# drive_subsystem.net
KiCad netlist of a schematic drawn in EAGLE
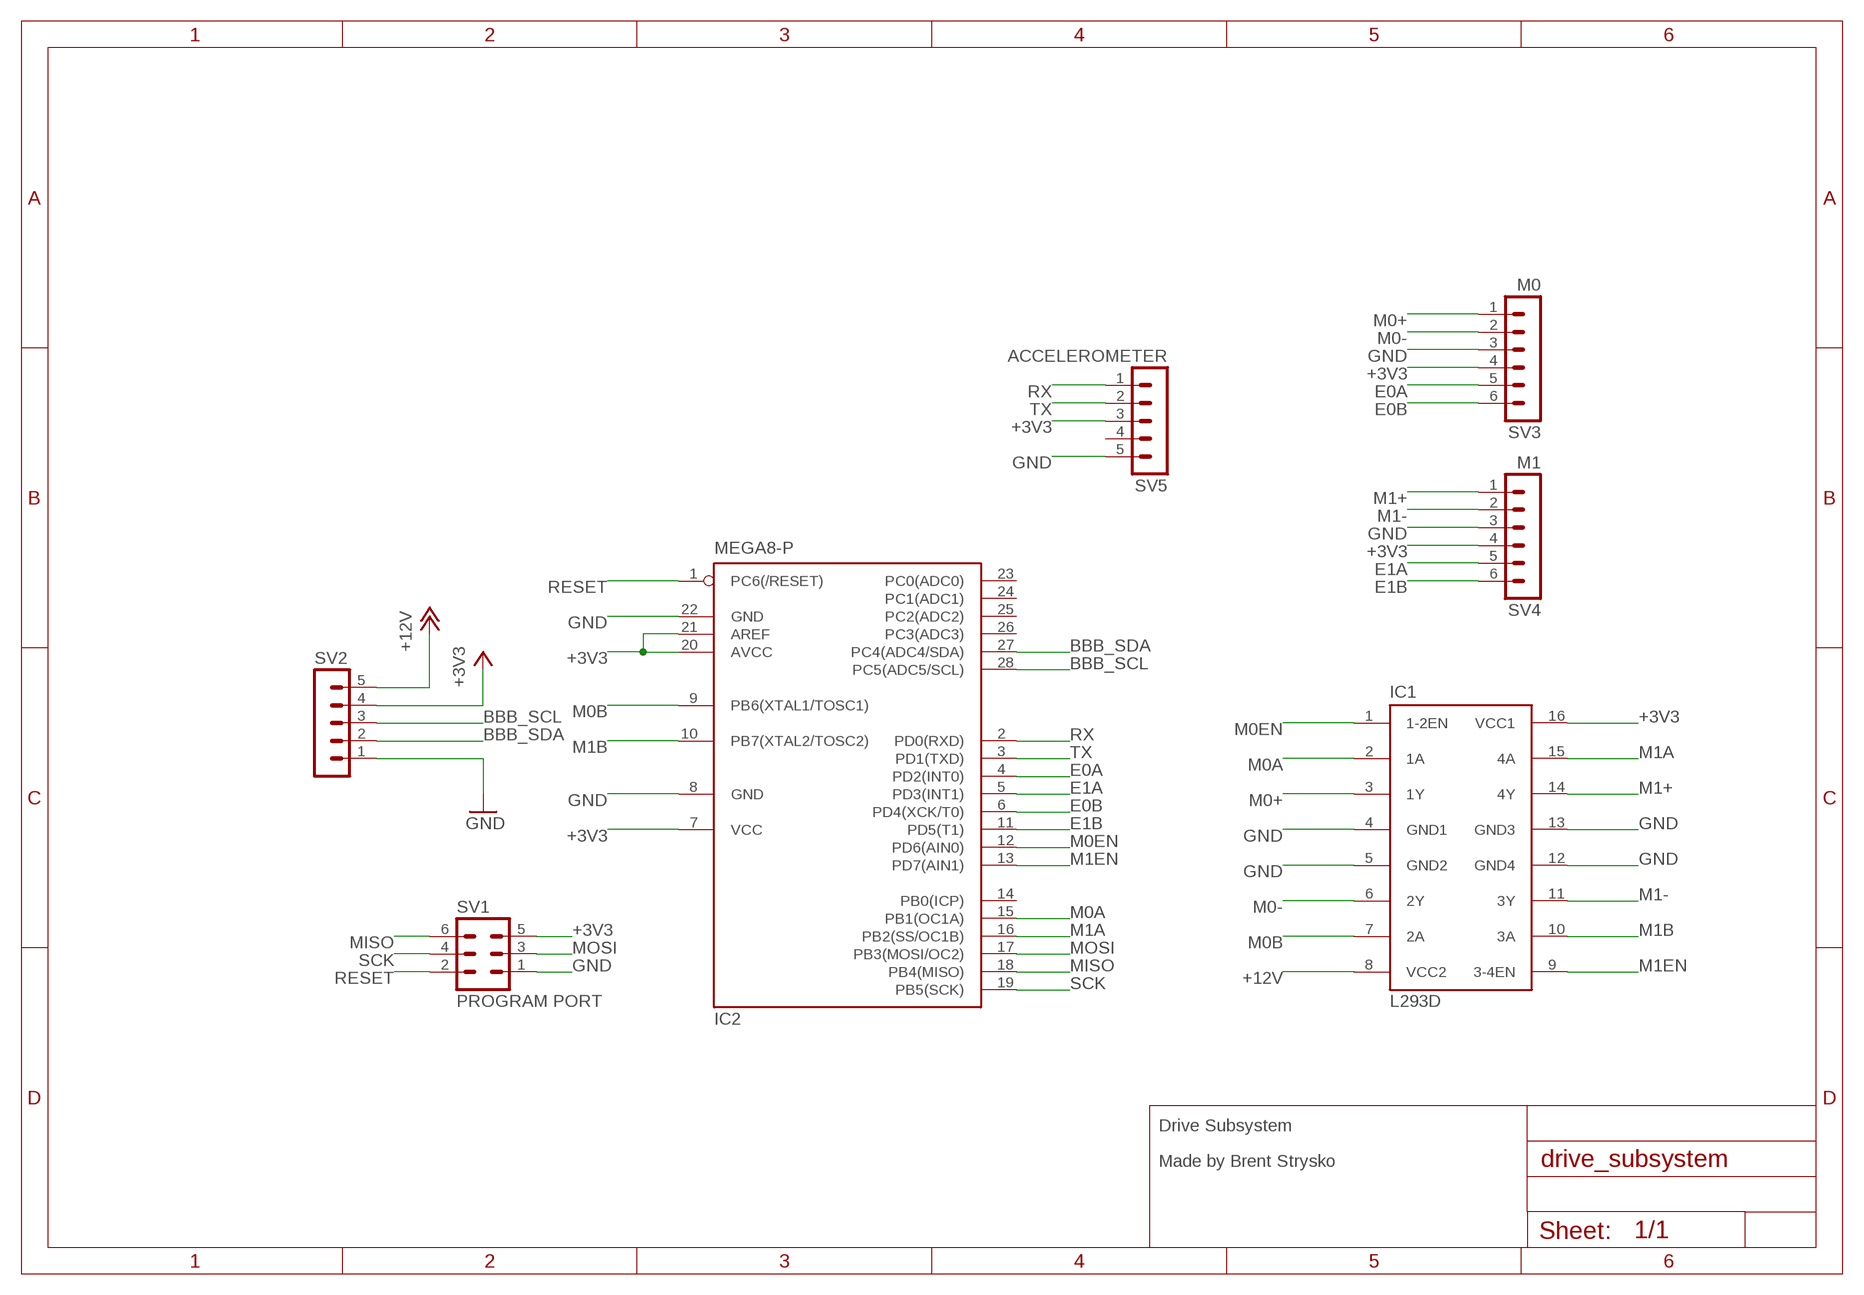
[diagram p0: schematic, sheet 1]

(export (version "E")
  (design (tool "Eeschema 10.0.6"))
  (components
    (comp (ref "IC1")
      (value "L293D")
      (footprint "eagle-import:DIL16")
      (libsource (lib "eagle-import") (part "L293D"))
    )
    (comp (ref "IC2")
      (value "MEGA8-P")
      (footprint "eagle-import:DIL28-3")
      (libsource (lib "eagle-import") (part "MEGA8-P"))
    )
    (comp (ref "SV1")
      (value "PROGRAM PORT")
      (footprint "eagle-import:MA03-2")
      (libsource (lib "eagle-import") (part "MA03-2"))
    )
    (comp (ref "SV2")
      (value "MA05-1")
      (footprint "eagle-import:MA05-1")
      (libsource (lib "eagle-import") (part "MA05-1"))
    )
    (comp (ref "SV3")
      (value "M0")
      (footprint "eagle-import:MA06-1")
      (libsource (lib "eagle-import") (part "MA06-1"))
    )
    (comp (ref "SV4")
      (value "M1")
      (footprint "eagle-import:MA06-1")
      (libsource (lib "eagle-import") (part "MA06-1"))
    )
    (comp (ref "SV5")
      (value "ACCELEROMETER")
      (footprint "eagle-import:MA05-1")
      (libsource (lib "eagle-import") (part "MA05-1"))
    )
  )
  (nets
    (net (code "1") (name "+3V3") (class "Default")
      (node (ref "IC1") (pin "16") (pinfunction "VCC1_16") (pintype "power_in"))
      (node (ref "IC2") (pin "20") (pinfunction "AVCC_20") (pintype "power_in"))
      (node (ref "IC2") (pin "21") (pinfunction "AREF_21") (pintype "passive"))
      (node (ref "IC2") (pin "7") (pinfunction "VCC_7") (pintype "power_in"))
      (node (ref "SV1") (pin "5") (pinfunction "5_5") (pintype "passive"))
      (node (ref "SV2") (pin "4") (pinfunction "4_4") (pintype "passive"))
      (node (ref "SV3") (pin "4") (pinfunction "4_4") (pintype "passive"))
      (node (ref "SV4") (pin "4") (pinfunction "4_4") (pintype "passive"))
      (node (ref "SV5") (pin "3") (pinfunction "3_3") (pintype "passive"))
    )
    (net (code "2") (name "+12V") (class "Default")
      (node (ref "IC1") (pin "8") (pinfunction "VCC2_8") (pintype "power_in"))
      (node (ref "SV2") (pin "5") (pinfunction "5_5") (pintype "passive"))
    )
    (net (code "3") (name "/BBB_SCL") (class "Default")
      (node (ref "IC2") (pin "28") (pinfunction "PC5(ADC5/SCL)_28") (pintype "bidirectional"))
      (node (ref "SV2") (pin "3") (pinfunction "3_3") (pintype "passive"))
    )
    (net (code "4") (name "/BBB_SDA") (class "Default")
      (node (ref "IC2") (pin "27") (pinfunction "PC4(ADC4/SDA)_27") (pintype "bidirectional"))
      (node (ref "SV2") (pin "2") (pinfunction "2_2") (pintype "passive"))
    )
    (net (code "5") (name "/E0A") (class "Default")
      (node (ref "IC2") (pin "4") (pinfunction "PD2(INT0)_4") (pintype "bidirectional"))
      (node (ref "SV3") (pin "5") (pinfunction "5_5") (pintype "passive"))
    )
    (net (code "6") (name "/E0B") (class "Default")
      (node (ref "IC2") (pin "6") (pinfunction "PD4(XCK/T0)_6") (pintype "bidirectional"))
      (node (ref "SV3") (pin "6") (pinfunction "6_6") (pintype "passive"))
    )
    (net (code "7") (name "/E1A") (class "Default")
      (node (ref "IC2") (pin "5") (pinfunction "PD3(INT1)_5") (pintype "bidirectional"))
      (node (ref "SV4") (pin "5") (pinfunction "5_5") (pintype "passive"))
    )
    (net (code "8") (name "/E1B") (class "Default")
      (node (ref "IC2") (pin "11") (pinfunction "PD5(T1)_11") (pintype "bidirectional"))
      (node (ref "SV4") (pin "6") (pinfunction "6_6") (pintype "passive"))
    )
    (net (code "9") (name "/M0+") (class "Default")
      (node (ref "IC1") (pin "3") (pinfunction "1Y_3") (pintype "output"))
      (node (ref "SV3") (pin "1") (pinfunction "1_1") (pintype "passive"))
    )
    (net (code "10") (name "/M0-") (class "Default")
      (node (ref "IC1") (pin "6") (pinfunction "2Y_6") (pintype "output"))
      (node (ref "SV3") (pin "2") (pinfunction "2_2") (pintype "passive"))
    )
    (net (code "11") (name "/M0A") (class "Default")
      (node (ref "IC1") (pin "2") (pinfunction "1A_2") (pintype "input"))
      (node (ref "IC2") (pin "15") (pinfunction "PB1(OC1A)_15") (pintype "bidirectional"))
    )
    (net (code "12") (name "/M0B") (class "Default")
      (node (ref "IC1") (pin "7") (pinfunction "2A_7") (pintype "input"))
      (node (ref "IC2") (pin "9") (pinfunction "PB6(XTAL1/TOSC1)_9") (pintype "bidirectional"))
    )
    (net (code "13") (name "/M0EN") (class "Default")
      (node (ref "IC1") (pin "1") (pinfunction "1-2EN_1") (pintype "input"))
      (node (ref "IC2") (pin "12") (pinfunction "PD6(AIN0)_12") (pintype "bidirectional"))
    )
    (net (code "14") (name "/M1+") (class "Default")
      (node (ref "IC1") (pin "14") (pinfunction "4Y_14") (pintype "output"))
      (node (ref "SV4") (pin "1") (pinfunction "1_1") (pintype "passive"))
    )
    (net (code "15") (name "/M1-") (class "Default")
      (node (ref "IC1") (pin "11") (pinfunction "3Y_11") (pintype "output"))
      (node (ref "SV4") (pin "2") (pinfunction "2_2") (pintype "passive"))
    )
    (net (code "16") (name "/M1A") (class "Default")
      (node (ref "IC1") (pin "15") (pinfunction "4A_15") (pintype "input"))
      (node (ref "IC2") (pin "16") (pinfunction "PB2(SS/OC1B)_16") (pintype "bidirectional"))
    )
    (net (code "17") (name "/M1B") (class "Default")
      (node (ref "IC1") (pin "10") (pinfunction "3A_10") (pintype "input"))
      (node (ref "IC2") (pin "10") (pinfunction "PB7(XTAL2/TOSC2)_10") (pintype "bidirectional"))
    )
    (net (code "18") (name "/M1EN") (class "Default")
      (node (ref "IC1") (pin "9") (pinfunction "3-4EN_9") (pintype "input"))
      (node (ref "IC2") (pin "13") (pinfunction "PD7(AIN1)_13") (pintype "bidirectional"))
    )
    (net (code "19") (name "/MISO") (class "Default")
      (node (ref "IC2") (pin "18") (pinfunction "PB4(MISO)_18") (pintype "bidirectional"))
      (node (ref "SV1") (pin "6") (pinfunction "6_6") (pintype "passive"))
    )
    (net (code "20") (name "/MOSI") (class "Default")
      (node (ref "IC2") (pin "17") (pinfunction "PB3(MOSI/OC2)_17") (pintype "bidirectional"))
      (node (ref "SV1") (pin "3") (pinfunction "3_3") (pintype "passive"))
    )
    (net (code "21") (name "/RESET") (class "Default")
      (node (ref "IC2") (pin "1") (pinfunction "PC6(/RESET)_1") (pintype "bidirectional"))
      (node (ref "SV1") (pin "2") (pinfunction "2_2") (pintype "passive"))
    )
    (net (code "22") (name "/RX") (class "Default")
      (node (ref "IC2") (pin "2") (pinfunction "PD0(RXD)_2") (pintype "bidirectional"))
      (node (ref "SV5") (pin "1") (pinfunction "1_1") (pintype "passive"))
    )
    (net (code "23") (name "/SCK") (class "Default")
      (node (ref "IC2") (pin "19") (pinfunction "PB5(SCK)_19") (pintype "bidirectional"))
      (node (ref "SV1") (pin "4") (pinfunction "4_4") (pintype "passive"))
    )
    (net (code "24") (name "/TX") (class "Default")
      (node (ref "IC2") (pin "3") (pinfunction "PD1(TXD)_3") (pintype "bidirectional"))
      (node (ref "SV5") (pin "2") (pinfunction "2_2") (pintype "passive"))
    )
    (net (code "25") (name "GND") (class "Default")
      (node (ref "IC1") (pin "12") (pinfunction "GND4_12") (pintype "power_in"))
      (node (ref "IC1") (pin "13") (pinfunction "GND3_13") (pintype "power_in"))
      (node (ref "IC1") (pin "4") (pinfunction "GND1_4") (pintype "power_in"))
      (node (ref "IC1") (pin "5") (pinfunction "GND2_5") (pintype "power_in"))
      (node (ref "IC2") (pin "22") (pinfunction "GND_22") (pintype "power_in"))
      (node (ref "IC2") (pin "8") (pinfunction "GND_8") (pintype "power_in"))
      (node (ref "SV1") (pin "1") (pinfunction "1_1") (pintype "passive"))
      (node (ref "SV2") (pin "1") (pinfunction "1_1") (pintype "passive"))
      (node (ref "SV3") (pin "3") (pinfunction "3_3") (pintype "passive"))
      (node (ref "SV4") (pin "3") (pinfunction "3_3") (pintype "passive"))
      (node (ref "SV5") (pin "5") (pinfunction "5_5") (pintype "passive"))
    )
    (net (code "26") (name "unconnected-(IC2-PB0(ICP)-Pad14)") (class "Default")
      (node (ref "IC2") (pin "14") (pinfunction "PB0(ICP)_14") (pintype "bidirectional"))
    )
    (net (code "27") (name "unconnected-(IC2-PC0(ADC0)-Pad23)") (class "Default")
      (node (ref "IC2") (pin "23") (pinfunction "PC0(ADC0)_23") (pintype "bidirectional"))
    )
    (net (code "28") (name "unconnected-(IC2-PC1(ADC1)-Pad24)") (class "Default")
      (node (ref "IC2") (pin "24") (pinfunction "PC1(ADC1)_24") (pintype "bidirectional"))
    )
    (net (code "29") (name "unconnected-(IC2-PC2(ADC2)-Pad25)") (class "Default")
      (node (ref "IC2") (pin "25") (pinfunction "PC2(ADC2)_25") (pintype "bidirectional"))
    )
    (net (code "30") (name "unconnected-(IC2-PC3(ADC3)-Pad26)") (class "Default")
      (node (ref "IC2") (pin "26") (pinfunction "PC3(ADC3)_26") (pintype "bidirectional"))
    )
    (net (code "31") (name "unconnected-(SV5-Pad4)") (class "Default")
      (node (ref "SV5") (pin "4") (pinfunction "4_4") (pintype "passive"))
    )
  )
)
